# Power.net
KiCad netlist of a schematic drawn in Altium Designer
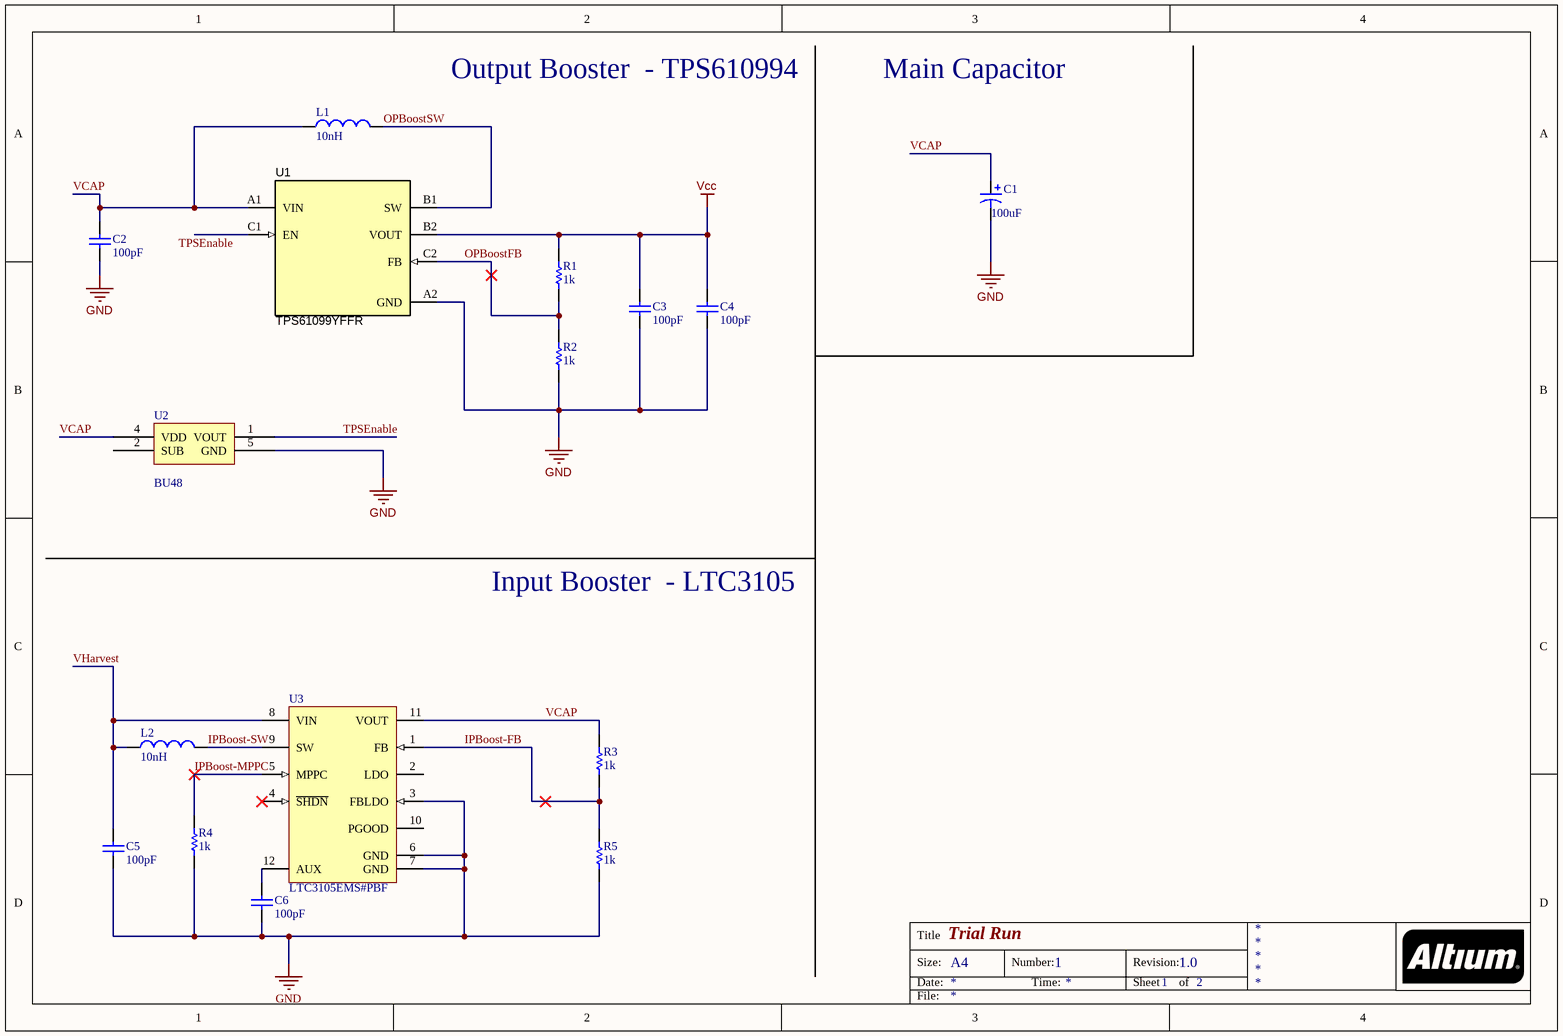
[diagram p0: Power.SchDoc]

(export (version "E")
  (design (tool "Eeschema 10.0.6"))
  (components
    (comp (ref "C1")
      (value "100uF")
      (description "Polarized Capacitor")
      (fields (field (name "Comment") "Cap - Polarized"))
      (libsource (lib "DRP_Basic_2014") (part "Cap - Polarized"))
    )
    (comp (ref "C2")
      (value "100pF")
      (footprint "0402")
      (description "Ceramic Capacitor (Surface Mount)")
      (fields (field (name "MANUFACTURER") "Generic Ceramic Chip Cap (TBD)") (field (name "Comment") "Cap"))
      (libsource (lib "DRP_Basic_2014") (part "Cap"))
    )
    (comp (ref "C3")
      (value "100pF")
      (footprint "0402")
      (description "Ceramic Capacitor (Surface Mount)")
      (fields (field (name "MANUFACTURER") "Generic Ceramic Chip Cap (TBD)") (field (name "Comment") "Cap"))
      (libsource (lib "DRP_Basic_2014") (part "Cap"))
    )
    (comp (ref "C4")
      (value "100pF")
      (footprint "0402")
      (description "Ceramic Capacitor (Surface Mount)")
      (fields (field (name "MANUFACTURER") "Generic Ceramic Chip Cap (TBD)") (field (name "Comment") "Cap"))
      (libsource (lib "DRP_Basic_2014") (part "Cap"))
    )
    (comp (ref "C5")
      (value "100pF")
      (footprint "0402")
      (description "Ceramic Capacitor (Surface Mount)")
      (fields (field (name "MANUFACTURER") "Generic Ceramic Chip Cap (TBD)") (field (name "Comment") "Cap"))
      (libsource (lib "DRP_Basic_2014") (part "Cap"))
    )
    (comp (ref "C6")
      (value "100pF")
      (footprint "0402")
      (description "Ceramic Capacitor (Surface Mount)")
      (fields (field (name "MANUFACTURER") "Generic Ceramic Chip Cap (TBD)") (field (name "Comment") "Cap"))
      (libsource (lib "DRP_Basic_2014") (part "Cap"))
    )
    (comp (ref "L1")
      (value "10nH")
      (footprint "0402")
      (description "Inductor (Surface Mount)")
      (fields (field (name "Comment") "Ind"))
      (libsource (lib "DRP_Basic_2014") (part "Ind"))
    )
    (comp (ref "L2")
      (value "10nH")
      (footprint "0402")
      (description "Inductor (Surface Mount)")
      (fields (field (name "Comment") "Ind"))
      (libsource (lib "DRP_Basic_2014") (part "Ind"))
    )
    (comp (ref "R1")
      (value "1k")
      (footprint "0402")
      (description "Chip Resistor (Surface Mount)")
      (fields (field (name "MANUFACTURER") "Generic Chip Res (TBD)") (field (name "Comment") "Res"))
      (libsource (lib "DRP_Basic_2014") (part "Res"))
    )
    (comp (ref "R2")
      (value "1k")
      (footprint "0402")
      (description "Chip Resistor (Surface Mount)")
      (fields (field (name "MANUFACTURER") "Generic Chip Res (TBD)") (field (name "Comment") "Res"))
      (libsource (lib "DRP_Basic_2014") (part "Res"))
    )
    (comp (ref "R3")
      (value "1k")
      (footprint "0402")
      (description "Chip Resistor (Surface Mount)")
      (fields (field (name "MANUFACTURER") "Generic Chip Res (TBD)") (field (name "Comment") "Res"))
      (libsource (lib "DRP_Basic_2014") (part "Res"))
    )
    (comp (ref "R4")
      (value "1k")
      (footprint "0402")
      (description "Chip Resistor (Surface Mount)")
      (fields (field (name "MANUFACTURER") "Generic Chip Res (TBD)") (field (name "Comment") "Res"))
      (libsource (lib "DRP_Basic_2014") (part "Res"))
    )
    (comp (ref "R5")
      (value "1k")
      (footprint "0402")
      (description "Chip Resistor (Surface Mount)")
      (fields (field (name "MANUFACTURER") "Generic Chip Res (TBD)") (field (name "Comment") "Res"))
      (libsource (lib "DRP_Basic_2014") (part "Res"))
    )
    (comp (ref "U1")
      (value "TPS61099YFFR")
      (footprint "YFF0006AFAD")
      (description "Synchronous Boost Converter with 800 nA Ultra-Low Quiescent Current, YFF0006AFAD (DSBGA-6)")
      (fields
        (field (name "ALTERNATE PARTNUMBER") "TPS61099YFFT")
        (field (name "MANUFACTURER") "Texas Instruments")
        (field (name "SYMBOLCREATOR") "Altium")
        (field (name "PUBLISHER") "Texas Instruments")
      )
      (libsource (lib "TI_Pre_Release1") (part "TPS61099YFFR"))
    )
    (comp (ref "U2")
      (value "BU48")
      (footprint "VSOF5")
      (description "IC DETECTOR OPEN-DRAIN")
      (fields (field (name "NAME") "BU48"))
      (libsource (lib "Sprite") (part "BU48"))
    )
    (comp (ref "U3")
      (value "LTC3105EMS#PBF")
      (footprint "LT-MS-12_N")
      (fields (field (name "MANUFACTURER") "Linear Technology"))
      (libsource (lib "Altium Content Vault") (part "LT-LTC3105-MS-12"))
    )
  )
  (nets
    (net (code "1") (name "/IPBoost-FB") (class "Default")
      (node (ref "R3") (pin "2") (pinfunction "2_2") (pintype "passive"))
      (node (ref "R5") (pin "1") (pinfunction "1_1") (pintype "passive"))
      (node (ref "U3") (pin "1") (pinfunction "FB_1") (pintype "input"))
    )
    (net (code "2") (name "/IPBoost-MPPC") (class "Default")
      (node (ref "R4") (pin "1") (pinfunction "1_1") (pintype "passive"))
      (node (ref "U3") (pin "5") (pinfunction "MPPC_5") (pintype "input"))
    )
    (net (code "3") (name "/IPBoost-SW") (class "Default")
      (node (ref "L2") (pin "2") (pinfunction "2_2") (pintype "passive"))
      (node (ref "U3") (pin "9") (pinfunction "SW_9") (pintype "power_in"))
    )
    (net (code "4") (name "/OPBoostFB") (class "Default")
      (node (ref "R1") (pin "1") (pinfunction "1_1") (pintype "passive"))
      (node (ref "R2") (pin "2") (pinfunction "2_2") (pintype "passive"))
      (node (ref "U1") (pin "C2") (pinfunction "FB_C2") (pintype "input"))
    )
    (net (code "5") (name "/OPBoostSW") (class "Default")
      (node (ref "L1") (pin "2") (pinfunction "2_2") (pintype "passive"))
      (node (ref "U1") (pin "B1") (pinfunction "SW_B1") (pintype "power_in"))
    )
    (net (code "6") (name "/TPSEnable") (class "Default")
      (node (ref "U1") (pin "C1") (pinfunction "EN_C1") (pintype "input"))
      (node (ref "U2") (pin "1") (pinfunction "VOUT_1") (pintype "open_collector"))
    )
    (net (code "7") (name "/VCAP") (class "Default")
      (node (ref "C1") (pin "1") (pinfunction "1_1") (pintype "passive"))
      (node (ref "C2") (pin "2") (pinfunction "2_2") (pintype "passive"))
      (node (ref "L1") (pin "1") (pinfunction "1_1") (pintype "passive"))
      (node (ref "R3") (pin "1") (pinfunction "1_1") (pintype "passive"))
      (node (ref "U1") (pin "A1") (pinfunction "VIN_A1") (pintype "power_in"))
      (node (ref "U2") (pin "4") (pinfunction "VDD_4") (pintype "power_in"))
      (node (ref "U3") (pin "11") (pinfunction "VOUT_11") (pintype "power_in"))
    )
    (net (code "8") (name "/VHarvest") (class "Default")
      (node (ref "C5") (pin "2") (pinfunction "2_2") (pintype "passive"))
      (node (ref "L2") (pin "1") (pinfunction "1_1") (pintype "passive"))
      (node (ref "U3") (pin "8") (pinfunction "VIN_8") (pintype "power_in"))
    )
    (net (code "9") (name "GND") (class "Default")
      (node (ref "C1") (pin "2") (pinfunction "2_2") (pintype "passive"))
      (node (ref "C2") (pin "1") (pinfunction "1_1") (pintype "passive"))
      (node (ref "C3") (pin "1") (pinfunction "1_1") (pintype "passive"))
      (node (ref "C4") (pin "1") (pinfunction "1_1") (pintype "passive"))
      (node (ref "C5") (pin "1") (pinfunction "1_1") (pintype "passive"))
      (node (ref "C6") (pin "1") (pinfunction "1_1") (pintype "passive"))
      (node (ref "R2") (pin "1") (pinfunction "1_1") (pintype "passive"))
      (node (ref "R4") (pin "2") (pinfunction "2_2") (pintype "passive"))
      (node (ref "R5") (pin "2") (pinfunction "2_2") (pintype "passive"))
      (node (ref "U1") (pin "A2") (pinfunction "GND_A2") (pintype "power_in"))
      (node (ref "U2") (pin "5") (pinfunction "GND_5") (pintype "power_in"))
      (node (ref "U3") (pin "3") (pinfunction "FBLDO_3") (pintype "input"))
      (node (ref "U3") (pin "6") (pinfunction "GND_6") (pintype "power_in"))
      (node (ref "U3") (pin "7") (pinfunction "GND_7") (pintype "power_in"))
    )
    (net (code "10") (name "Net-(U3-AUX)") (class "Default")
      (node (ref "C6") (pin "2") (pinfunction "2_2") (pintype "passive"))
      (node (ref "U3") (pin "12") (pinfunction "AUX_12") (pintype "power_in"))
    )
    (net (code "11") (name "Vcc") (class "Default")
      (node (ref "C3") (pin "2") (pinfunction "2_2") (pintype "passive"))
      (node (ref "C4") (pin "2") (pinfunction "2_2") (pintype "passive"))
      (node (ref "R1") (pin "2") (pinfunction "2_2") (pintype "passive"))
      (node (ref "U1") (pin "B2") (pinfunction "VOUT_B2") (pintype "power_in"))
    )
    (net (code "12") (name "unconnected-(U2-SUB-Pad2)") (class "Default")
      (node (ref "U2") (pin "2") (pinfunction "SUB_2") (pintype "passive"))
    )
    (net (code "13") (name "unconnected-(U3-LDO-Pad2)") (class "Default")
      (node (ref "U3") (pin "2") (pinfunction "LDO_2") (pintype "power_in"))
    )
    (net (code "14") (name "unconnected-(U3-PGOOD-Pad10)") (class "Default")
      (node (ref "U3") (pin "10") (pinfunction "PGOOD_10") (pintype "open_collector"))
    )
    (net (code "15") (name "unconnected-(U3-~{SHDN}-Pad4)") (class "Default")
      (node (ref "U3") (pin "4") (pinfunction "~{SHDN}_4") (pintype "input+no_connect"))
    )
  )
)
